# TuringBack.net
KiCad netlist of a schematic drawn in EAGLE
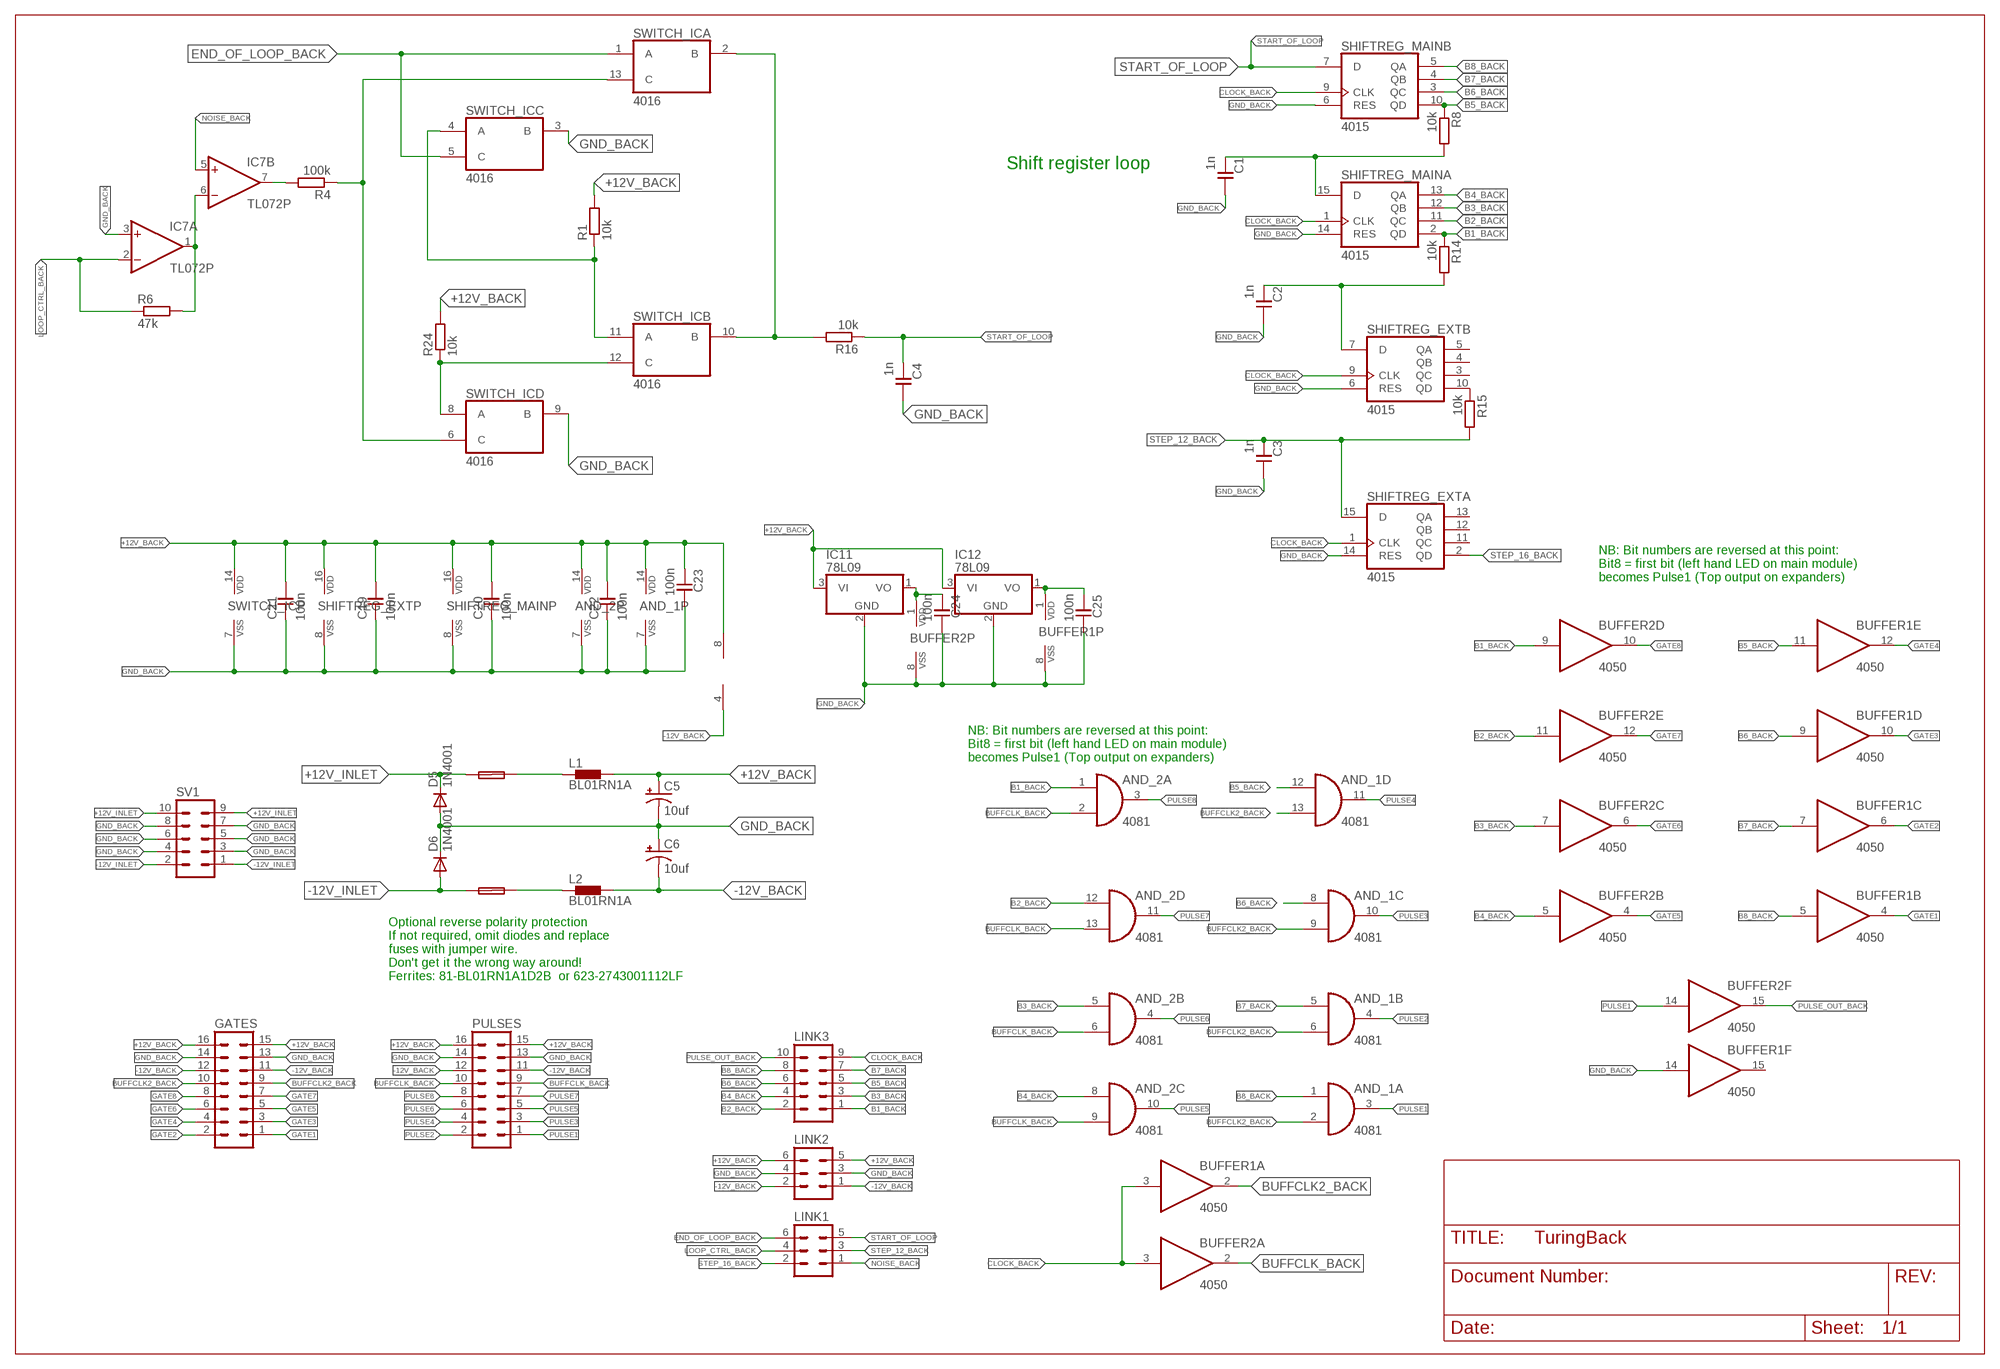
[diagram p0: schematic, sheet 1]

(export (version "E")
  (design (tool "Eeschema 10.0.6"))
  (components
    (comp (ref "+FUSE")
      (value "+FUSE")
      (footprint "eagle-import:C050H075X075")
      (libsource (lib "eagle-import") (part "PTC_FUSEPOLY_FUSE"))
    )
    (comp (ref "-FUSE")
      (value "-FUSE")
      (footprint "eagle-import:C050H075X075")
      (libsource (lib "eagle-import") (part "PTC_FUSEPOLY_FUSE"))
    )
    (comp (ref "AND_1")
      (value "4081")
      (footprint "eagle-import:DIL14")
      (libsource (lib "eagle-import") (part "4081N"))
    )
    (comp (ref "AND_2")
      (value "4081")
      (footprint "eagle-import:DIL14")
      (libsource (lib "eagle-import") (part "4081N"))
    )
    (comp (ref "BUFFER1")
      (value "4050")
      (footprint "eagle-import:DIL16")
      (libsource (lib "eagle-import") (part "4050N"))
    )
    (comp (ref "BUFFER2")
      (value "4050")
      (footprint "eagle-import:DIL16")
      (libsource (lib "eagle-import") (part "4050N"))
    )
    (comp (ref "C1")
      (value "1n")
      (footprint "eagle-import:C050-024X044")
      (libsource (lib "eagle-import") (part "C-EU050-024X044"))
    )
    (comp (ref "C2")
      (value "1n")
      (footprint "eagle-import:C050-024X044")
      (libsource (lib "eagle-import") (part "C-EU050-024X044"))
    )
    (comp (ref "C3")
      (value "1n")
      (footprint "eagle-import:C050-024X044")
      (libsource (lib "eagle-import") (part "C-EU050-024X044"))
    )
    (comp (ref "C4")
      (value "1n")
      (footprint "eagle-import:C050-024X044")
      (libsource (lib "eagle-import") (part "C-EU050-024X044"))
    )
    (comp (ref "C5")
      (value "10uf")
      (footprint "eagle-import:CPOL-RADIAL-10UF-25V")
      (libsource (lib "eagle-import") (part "CAP_POLPTH2"))
    )
    (comp (ref "C6")
      (value "10uf")
      (footprint "eagle-import:CPOL-RADIAL-10UF-25V")
      (libsource (lib "eagle-import") (part "CAP_POLPTH2"))
    )
    (comp (ref "C19")
      (value "100n")
      (footprint "eagle-import:C050-024X044")
      (libsource (lib "eagle-import") (part "C-EU050-024X044"))
    )
    (comp (ref "C20")
      (value "100n")
      (footprint "eagle-import:C050-024X044")
      (libsource (lib "eagle-import") (part "C-EU050-024X044"))
    )
    (comp (ref "C21")
      (value "100n")
      (footprint "eagle-import:C050-024X044")
      (libsource (lib "eagle-import") (part "C-EU050-024X044"))
    )
    (comp (ref "C22")
      (value "100n")
      (footprint "eagle-import:C050-024X044")
      (libsource (lib "eagle-import") (part "C-EU050-024X044"))
    )
    (comp (ref "C23")
      (value "100n")
      (footprint "eagle-import:C050-024X044")
      (libsource (lib "eagle-import") (part "C-EU050-024X044"))
    )
    (comp (ref "C24")
      (value "100n")
      (footprint "eagle-import:C050-024X044")
      (libsource (lib "eagle-import") (part "C-EU050-024X044"))
    )
    (comp (ref "C25")
      (value "100n")
      (footprint "eagle-import:C050-024X044")
      (libsource (lib "eagle-import") (part "C-EU050-024X044"))
    )
    (comp (ref "D5")
      (value "1N4001")
      (footprint "eagle-import:DO41-10")
      (libsource (lib "eagle-import") (part "1N4004"))
    )
    (comp (ref "D6")
      (value "1N4001")
      (footprint "eagle-import:DO41-10")
      (libsource (lib "eagle-import") (part "1N4004"))
    )
    (comp (ref "GATES")
      (value "MA08-2")
      (footprint "eagle-import:MA08-2")
      (libsource (lib "eagle-import") (part "MA08-2"))
    )
    (comp (ref "IC7")
      (value "TL072P")
      (footprint "eagle-import:DIL08")
      (libsource (lib "eagle-import") (part "TL072P"))
    )
    (comp (ref "IC11")
      (value "78L09")
      (footprint "eagle-import:TO92")
      (libsource (lib "eagle-import") (part "78L08"))
    )
    (comp (ref "IC12")
      (value "78L09")
      (footprint "eagle-import:TO92")
      (libsource (lib "eagle-import") (part "78L08"))
    )
    (comp (ref "L1")
      (value "BL01RN1A")
      (footprint "eagle-import:BL01RN1A")
      (libsource (lib "eagle-import") (part "BL01RN1A"))
    )
    (comp (ref "L2")
      (value "BL01RN1A")
      (footprint "eagle-import:BL01RN1A")
      (libsource (lib "eagle-import") (part "BL01RN1A"))
    )
    (comp (ref "LINK1")
      (value "MA03-2")
      (footprint "eagle-import:MA03-2")
      (libsource (lib "eagle-import") (part "MA03-2"))
    )
    (comp (ref "LINK2")
      (value "MA03-2")
      (footprint "eagle-import:MA03-2")
      (libsource (lib "eagle-import") (part "MA03-2"))
    )
    (comp (ref "LINK3")
      (value "MA05-2")
      (footprint "eagle-import:MA05-2")
      (libsource (lib "eagle-import") (part "MA05-2"))
    )
    (comp (ref "PULSES")
      (value "MA08-2")
      (footprint "eagle-import:MA08-2")
      (libsource (lib "eagle-import") (part "MA08-2"))
    )
    (comp (ref "R1")
      (value "10k")
      (footprint "eagle-import:0207_7")
      (libsource (lib "eagle-import") (part "R-EU_0207/7"))
    )
    (comp (ref "R4")
      (value "100k")
      (footprint "eagle-import:0207_7")
      (libsource (lib "eagle-import") (part "R-EU_0207/7"))
    )
    (comp (ref "R6")
      (value "47k")
      (footprint "eagle-import:0207_7")
      (libsource (lib "eagle-import") (part "R-EU_0207/7"))
    )
    (comp (ref "R8")
      (value "10k")
      (footprint "eagle-import:0207_7")
      (libsource (lib "eagle-import") (part "R-EU_0207/7"))
    )
    (comp (ref "R14")
      (value "10k")
      (footprint "eagle-import:0207_7")
      (libsource (lib "eagle-import") (part "R-EU_0207/7"))
    )
    (comp (ref "R15")
      (value "10k")
      (footprint "eagle-import:0207_7")
      (libsource (lib "eagle-import") (part "R-EU_0207/7"))
    )
    (comp (ref "R16")
      (value "10k")
      (footprint "eagle-import:0207_7")
      (libsource (lib "eagle-import") (part "R-EU_0207/7"))
    )
    (comp (ref "R24")
      (value "10k")
      (footprint "eagle-import:0207_7")
      (libsource (lib "eagle-import") (part "R-EU_0207/7"))
    )
    (comp (ref "SHIFTREG_EXT")
      (value "4015")
      (footprint "eagle-import:DIL16")
      (libsource (lib "eagle-import") (part "4015N"))
    )
    (comp (ref "SHIFTREG_MAIN")
      (value "4015")
      (footprint "eagle-import:DIL16")
      (libsource (lib "eagle-import") (part "4015N"))
    )
    (comp (ref "SV1")
      (value "10_PIN_HEADER")
      (footprint "eagle-import:MA05-2")
      (libsource (lib "eagle-import") (part "10_PIN_HEADER"))
    )
    (comp (ref "SWITCH_IC")
      (value "4016")
      (footprint "eagle-import:DIL14")
      (libsource (lib "eagle-import") (part "4016N"))
    )
  )
  (nets
    (net (code "1") (name "+12V_BACK") (class "Default")
      (node (ref "AND_1") (pin "14") (pinfunction "VDD_14") (pintype "power_in"))
      (node (ref "AND_2") (pin "14") (pinfunction "VDD_14") (pintype "power_in"))
      (node (ref "C19") (pin "1") (pinfunction "1_1") (pintype "passive"))
      (node (ref "C20") (pin "1") (pinfunction "1_1") (pintype "passive"))
      (node (ref "C21") (pin "1") (pinfunction "1_1") (pintype "passive"))
      (node (ref "C22") (pin "1") (pinfunction "1_1") (pintype "passive"))
      (node (ref "C23") (pin "2") (pinfunction "2_2") (pintype "passive"))
      (node (ref "C5") (pin "1") (pinfunction "+_1") (pintype "passive"))
      (node (ref "GATES") (pin "15") (pinfunction "15_15") (pintype "passive"))
      (node (ref "GATES") (pin "16") (pinfunction "16_16") (pintype "passive"))
      (node (ref "IC11") (pin "3") (pinfunction "VI_3") (pintype "input"))
      (node (ref "IC12") (pin "3") (pinfunction "VI_3") (pintype "input"))
      (node (ref "IC7") (pin "8") (pinfunction "V+_8") (pintype "power_in"))
      (node (ref "L1") (pin "2") (pinfunction "2_2") (pintype "passive"))
      (node (ref "LINK2") (pin "5") (pinfunction "5_5") (pintype "passive"))
      (node (ref "LINK2") (pin "6") (pinfunction "6_6") (pintype "passive"))
      (node (ref "PULSES") (pin "15") (pinfunction "15_15") (pintype "passive"))
      (node (ref "PULSES") (pin "16") (pinfunction "16_16") (pintype "passive"))
      (node (ref "R1") (pin "2") (pinfunction "2_2") (pintype "passive"))
      (node (ref "R24") (pin "2") (pinfunction "2_2") (pintype "passive"))
      (node (ref "SHIFTREG_EXT") (pin "16") (pinfunction "VDD_16") (pintype "power_in"))
      (node (ref "SHIFTREG_MAIN") (pin "16") (pinfunction "VDD_16") (pintype "power_in"))
      (node (ref "SWITCH_IC") (pin "14") (pinfunction "VDD_14") (pintype "power_in"))
    )
    (net (code "2") (name "+12V_INLET") (class "Default")
      (node (ref "+FUSE") (pin "1") (pinfunction "P$1_1") (pintype "bidirectional"))
      (node (ref "D5") (pin "C") (pinfunction "C_C") (pintype "passive"))
      (node (ref "SV1") (pin "10") (pinfunction "10_10") (pintype "passive"))
      (node (ref "SV1") (pin "9") (pinfunction "9_9") (pintype "passive"))
    )
    (net (code "3") (name "-12V_BACK") (class "Default")
      (node (ref "C6") (pin "2") (pinfunction "-_2") (pintype "passive"))
      (node (ref "GATES") (pin "11") (pinfunction "11_11") (pintype "passive"))
      (node (ref "GATES") (pin "12") (pinfunction "12_12") (pintype "passive"))
      (node (ref "IC7") (pin "4") (pinfunction "V-_4") (pintype "power_in"))
      (node (ref "L2") (pin "2") (pinfunction "2_2") (pintype "passive"))
      (node (ref "LINK2") (pin "1") (pinfunction "1_1") (pintype "passive"))
      (node (ref "LINK2") (pin "2") (pinfunction "2_2") (pintype "passive"))
      (node (ref "PULSES") (pin "11") (pinfunction "11_11") (pintype "passive"))
      (node (ref "PULSES") (pin "12") (pinfunction "12_12") (pintype "passive"))
    )
    (net (code "4") (name "-12V_INLET") (class "Default")
      (node (ref "-FUSE") (pin "1") (pinfunction "P$1_1") (pintype "bidirectional"))
      (node (ref "D6") (pin "A") (pinfunction "A_A") (pintype "passive"))
      (node (ref "SV1") (pin "1") (pinfunction "1_1") (pintype "passive"))
      (node (ref "SV1") (pin "2") (pinfunction "2_2") (pintype "passive"))
    )
    (net (code "5") (name "B1_BACK") (class "Default")
      (node (ref "AND_2") (pin "1") (pinfunction "I0_1") (pintype "input"))
      (node (ref "BUFFER2") (pin "9") (pinfunction "I_9") (pintype "input"))
      (node (ref "LINK3") (pin "1") (pinfunction "1_1") (pintype "passive"))
      (node (ref "R14") (pin "1") (pinfunction "1_1") (pintype "passive"))
      (node (ref "SHIFTREG_MAIN") (pin "2") (pinfunction "QD_2") (pintype "output"))
    )
    (net (code "6") (name "B2_BACK") (class "Default")
      (node (ref "AND_2") (pin "12") (pinfunction "I0_12") (pintype "input"))
      (node (ref "BUFFER2") (pin "11") (pinfunction "I_11") (pintype "input"))
      (node (ref "LINK3") (pin "2") (pinfunction "2_2") (pintype "passive"))
      (node (ref "SHIFTREG_MAIN") (pin "11") (pinfunction "QC_11") (pintype "output"))
    )
    (net (code "7") (name "B3_BACK") (class "Default")
      (node (ref "AND_2") (pin "5") (pinfunction "I0_5") (pintype "input"))
      (node (ref "BUFFER2") (pin "7") (pinfunction "I_7") (pintype "input"))
      (node (ref "LINK3") (pin "3") (pinfunction "3_3") (pintype "passive"))
      (node (ref "SHIFTREG_MAIN") (pin "12") (pinfunction "QB_12") (pintype "output"))
    )
    (net (code "8") (name "B4_BACK") (class "Default")
      (node (ref "AND_2") (pin "8") (pinfunction "I0_8") (pintype "input"))
      (node (ref "BUFFER2") (pin "5") (pinfunction "I_5") (pintype "input"))
      (node (ref "LINK3") (pin "4") (pinfunction "4_4") (pintype "passive"))
      (node (ref "SHIFTREG_MAIN") (pin "13") (pinfunction "QA_13") (pintype "output"))
    )
    (net (code "9") (name "B5_BACK") (class "Default")
      (node (ref "AND_1") (pin "12") (pinfunction "I0_12") (pintype "input"))
      (node (ref "BUFFER1") (pin "11") (pinfunction "I_11") (pintype "input"))
      (node (ref "LINK3") (pin "5") (pinfunction "5_5") (pintype "passive"))
      (node (ref "R8") (pin "1") (pinfunction "1_1") (pintype "passive"))
      (node (ref "SHIFTREG_MAIN") (pin "10") (pinfunction "QD_10") (pintype "output"))
    )
    (net (code "10") (name "B6_BACK") (class "Default")
      (node (ref "AND_1") (pin "8") (pinfunction "I0_8") (pintype "input"))
      (node (ref "BUFFER1") (pin "9") (pinfunction "I_9") (pintype "input"))
      (node (ref "LINK3") (pin "6") (pinfunction "6_6") (pintype "passive"))
      (node (ref "SHIFTREG_MAIN") (pin "3") (pinfunction "QC_3") (pintype "output"))
    )
    (net (code "11") (name "B7_BACK") (class "Default")
      (node (ref "AND_1") (pin "5") (pinfunction "I0_5") (pintype "input"))
      (node (ref "BUFFER1") (pin "7") (pinfunction "I_7") (pintype "input"))
      (node (ref "LINK3") (pin "7") (pinfunction "7_7") (pintype "passive"))
      (node (ref "SHIFTREG_MAIN") (pin "4") (pinfunction "QB_4") (pintype "output"))
    )
    (net (code "12") (name "B8_BACK") (class "Default")
      (node (ref "AND_1") (pin "1") (pinfunction "I0_1") (pintype "input"))
      (node (ref "BUFFER1") (pin "5") (pinfunction "I_5") (pintype "input"))
      (node (ref "LINK3") (pin "8") (pinfunction "8_8") (pintype "passive"))
      (node (ref "SHIFTREG_MAIN") (pin "5") (pinfunction "QA_5") (pintype "output"))
    )
    (net (code "13") (name "BUFFCLK2_BACK") (class "Default")
      (node (ref "AND_1") (pin "13") (pinfunction "I1_13") (pintype "input"))
      (node (ref "AND_1") (pin "2") (pinfunction "I1_2") (pintype "input"))
      (node (ref "AND_1") (pin "6") (pinfunction "I1_6") (pintype "input"))
      (node (ref "AND_1") (pin "9") (pinfunction "I1_9") (pintype "input"))
      (node (ref "BUFFER1") (pin "2") (pinfunction "O_2") (pintype "output"))
      (node (ref "GATES") (pin "10") (pinfunction "10_10") (pintype "passive"))
      (node (ref "GATES") (pin "9") (pinfunction "9_9") (pintype "passive"))
    )
    (net (code "14") (name "BUFFCLK_BACK") (class "Default")
      (node (ref "AND_2") (pin "13") (pinfunction "I1_13") (pintype "input"))
      (node (ref "AND_2") (pin "2") (pinfunction "I1_2") (pintype "input"))
      (node (ref "AND_2") (pin "6") (pinfunction "I1_6") (pintype "input"))
      (node (ref "AND_2") (pin "9") (pinfunction "I1_9") (pintype "input"))
      (node (ref "BUFFER2") (pin "2") (pinfunction "O_2") (pintype "output"))
      (node (ref "PULSES") (pin "10") (pinfunction "10_10") (pintype "passive"))
      (node (ref "PULSES") (pin "9") (pinfunction "9_9") (pintype "passive"))
    )
    (net (code "15") (name "CLOCK_BACK") (class "Default")
      (node (ref "BUFFER1") (pin "3") (pinfunction "I_3") (pintype "input"))
      (node (ref "BUFFER2") (pin "3") (pinfunction "I_3") (pintype "input"))
      (node (ref "LINK3") (pin "9") (pinfunction "9_9") (pintype "passive"))
      (node (ref "SHIFTREG_EXT") (pin "1") (pinfunction "CLK_1") (pintype "input"))
      (node (ref "SHIFTREG_EXT") (pin "9") (pinfunction "CLK_9") (pintype "input"))
      (node (ref "SHIFTREG_MAIN") (pin "1") (pinfunction "CLK_1") (pintype "input"))
      (node (ref "SHIFTREG_MAIN") (pin "9") (pinfunction "CLK_9") (pintype "input"))
    )
    (net (code "16") (name "END_OF_LOOP_BACK") (class "Default")
      (node (ref "LINK1") (pin "6") (pinfunction "6_6") (pintype "passive"))
      (node (ref "SWITCH_IC") (pin "1") (pinfunction "A_1") (pintype "tri_state"))
      (node (ref "SWITCH_IC") (pin "5") (pinfunction "C_5") (pintype "input"))
    )
    (net (code "17") (name "GATE1") (class "Default")
      (node (ref "BUFFER1") (pin "4") (pinfunction "O_4") (pintype "output"))
      (node (ref "GATES") (pin "1") (pinfunction "1_1") (pintype "passive"))
    )
    (net (code "18") (name "GATE2") (class "Default")
      (node (ref "BUFFER1") (pin "6") (pinfunction "O_6") (pintype "output"))
      (node (ref "GATES") (pin "2") (pinfunction "2_2") (pintype "passive"))
    )
    (net (code "19") (name "GATE3") (class "Default")
      (node (ref "BUFFER1") (pin "10") (pinfunction "O_10") (pintype "output"))
      (node (ref "GATES") (pin "3") (pinfunction "3_3") (pintype "passive"))
    )
    (net (code "20") (name "GATE4") (class "Default")
      (node (ref "BUFFER1") (pin "12") (pinfunction "O_12") (pintype "output"))
      (node (ref "GATES") (pin "4") (pinfunction "4_4") (pintype "passive"))
    )
    (net (code "21") (name "GATE5") (class "Default")
      (node (ref "BUFFER2") (pin "4") (pinfunction "O_4") (pintype "output"))
      (node (ref "GATES") (pin "5") (pinfunction "5_5") (pintype "passive"))
    )
    (net (code "22") (name "GATE6") (class "Default")
      (node (ref "BUFFER2") (pin "6") (pinfunction "O_6") (pintype "output"))
      (node (ref "GATES") (pin "6") (pinfunction "6_6") (pintype "passive"))
    )
    (net (code "23") (name "GATE7") (class "Default")
      (node (ref "BUFFER2") (pin "12") (pinfunction "O_12") (pintype "output"))
      (node (ref "GATES") (pin "7") (pinfunction "7_7") (pintype "passive"))
    )
    (net (code "24") (name "GATE8") (class "Default")
      (node (ref "BUFFER2") (pin "10") (pinfunction "O_10") (pintype "output"))
      (node (ref "GATES") (pin "8") (pinfunction "8_8") (pintype "passive"))
    )
    (net (code "25") (name "GND_BACK") (class "Default")
      (node (ref "AND_1") (pin "7") (pinfunction "VSS_7") (pintype "power_in"))
      (node (ref "AND_2") (pin "7") (pinfunction "VSS_7") (pintype "power_in"))
      (node (ref "BUFFER1") (pin "14") (pinfunction "I_14") (pintype "input"))
      (node (ref "BUFFER1") (pin "8") (pinfunction "VSS_8") (pintype "power_in"))
      (node (ref "BUFFER2") (pin "8") (pinfunction "VSS_8") (pintype "power_in"))
      (node (ref "C1") (pin "1") (pinfunction "1_1") (pintype "passive"))
      (node (ref "C19") (pin "2") (pinfunction "2_2") (pintype "passive"))
      (node (ref "C2") (pin "1") (pinfunction "1_1") (pintype "passive"))
      (node (ref "C20") (pin "2") (pinfunction "2_2") (pintype "passive"))
      (node (ref "C21") (pin "2") (pinfunction "2_2") (pintype "passive"))
      (node (ref "C22") (pin "2") (pinfunction "2_2") (pintype "passive"))
      (node (ref "C23") (pin "1") (pinfunction "1_1") (pintype "passive"))
      (node (ref "C24") (pin "1") (pinfunction "1_1") (pintype "passive"))
      (node (ref "C25") (pin "1") (pinfunction "1_1") (pintype "passive"))
      (node (ref "C3") (pin "1") (pinfunction "1_1") (pintype "passive"))
      (node (ref "C4") (pin "1") (pinfunction "1_1") (pintype "passive"))
      (node (ref "C5") (pin "2") (pinfunction "-_2") (pintype "passive"))
      (node (ref "C6") (pin "1") (pinfunction "+_1") (pintype "passive"))
      (node (ref "D5") (pin "A") (pinfunction "A_A") (pintype "passive"))
      (node (ref "D6") (pin "C") (pinfunction "C_C") (pintype "passive"))
      (node (ref "GATES") (pin "13") (pinfunction "13_13") (pintype "passive"))
      (node (ref "GATES") (pin "14") (pinfunction "14_14") (pintype "passive"))
      (node (ref "IC11") (pin "2") (pinfunction "GND_2") (pintype "passive"))
      (node (ref "IC12") (pin "2") (pinfunction "GND_2") (pintype "passive"))
      (node (ref "IC7") (pin "3") (pinfunction "+IN_3") (pintype "input"))
      (node (ref "LINK2") (pin "3") (pinfunction "3_3") (pintype "passive"))
      (node (ref "LINK2") (pin "4") (pinfunction "4_4") (pintype "passive"))
      (node (ref "PULSES") (pin "13") (pinfunction "13_13") (pintype "passive"))
      (node (ref "PULSES") (pin "14") (pinfunction "14_14") (pintype "passive"))
      (node (ref "SHIFTREG_EXT") (pin "14") (pinfunction "RES_14") (pintype "input"))
      (node (ref "SHIFTREG_EXT") (pin "6") (pinfunction "RES_6") (pintype "input"))
      (node (ref "SHIFTREG_EXT") (pin "8") (pinfunction "VSS_8") (pintype "power_in"))
      (node (ref "SHIFTREG_MAIN") (pin "14") (pinfunction "RES_14") (pintype "input"))
      (node (ref "SHIFTREG_MAIN") (pin "6") (pinfunction "RES_6") (pintype "input"))
      (node (ref "SHIFTREG_MAIN") (pin "8") (pinfunction "VSS_8") (pintype "power_in"))
      (node (ref "SV1") (pin "3") (pinfunction "3_3") (pintype "passive"))
      (node (ref "SV1") (pin "4") (pinfunction "4_4") (pintype "passive"))
      (node (ref "SV1") (pin "5") (pinfunction "5_5") (pintype "passive"))
      (node (ref "SV1") (pin "6") (pinfunction "6_6") (pintype "passive"))
      (node (ref "SV1") (pin "7") (pinfunction "7_7") (pintype "passive"))
      (node (ref "SV1") (pin "8") (pinfunction "8_8") (pintype "passive"))
      (node (ref "SWITCH_IC") (pin "3") (pinfunction "B_3") (pintype "tri_state"))
      (node (ref "SWITCH_IC") (pin "7") (pinfunction "VSS_7") (pintype "power_in"))
      (node (ref "SWITCH_IC") (pin "9") (pinfunction "B_9") (pintype "tri_state"))
    )
    (net (code "26") (name "LOOP_CTRL_BACK") (class "Default")
      (node (ref "IC7") (pin "2") (pinfunction "-IN_2") (pintype "input"))
      (node (ref "LINK1") (pin "4") (pinfunction "4_4") (pintype "passive"))
      (node (ref "R6") (pin "1") (pinfunction "1_1") (pintype "passive"))
    )
    (net (code "27") (name "NOISE_BACK") (class "Default")
      (node (ref "IC7") (pin "5") (pinfunction "+IN_5") (pintype "input"))
      (node (ref "LINK1") (pin "1") (pinfunction "1_1") (pintype "passive"))
    )
    (net (code "28") (name "Net-(+FUSE-P$2)") (class "Default")
      (node (ref "+FUSE") (pin "2") (pinfunction "P$2_2") (pintype "bidirectional"))
      (node (ref "L1") (pin "1") (pinfunction "1_1") (pintype "passive"))
    )
    (net (code "29") (name "Net-(-FUSE-P$2)") (class "Default")
      (node (ref "-FUSE") (pin "2") (pinfunction "P$2_2") (pintype "bidirectional"))
      (node (ref "L2") (pin "1") (pinfunction "1_1") (pintype "passive"))
    )
    (net (code "30") (name "Net-(BUFFER1G-VDD)") (class "Default")
      (node (ref "BUFFER1") (pin "1") (pinfunction "VDD_1") (pintype "power_in"))
      (node (ref "C25") (pin "2") (pinfunction "2_2") (pintype "passive"))
      (node (ref "IC12") (pin "1") (pinfunction "VO_1") (pintype "passive"))
    )
    (net (code "31") (name "Net-(BUFFER2G-VDD)") (class "Default")
      (node (ref "BUFFER2") (pin "1") (pinfunction "VDD_1") (pintype "power_in"))
      (node (ref "C24") (pin "2") (pinfunction "2_2") (pintype "passive"))
      (node (ref "IC11") (pin "1") (pinfunction "VO_1") (pintype "passive"))
    )
    (net (code "32") (name "Net-(IC7A-OUT)") (class "Default")
      (node (ref "IC7") (pin "1") (pinfunction "OUT_1") (pintype "output"))
      (node (ref "IC7") (pin "6") (pinfunction "-IN_6") (pintype "input"))
      (node (ref "R6") (pin "2") (pinfunction "2_2") (pintype "passive"))
    )
    (net (code "33") (name "Net-(IC7B-OUT)") (class "Default")
      (node (ref "IC7") (pin "7") (pinfunction "OUT_7") (pintype "output"))
      (node (ref "R4") (pin "2") (pinfunction "2_2") (pintype "passive"))
    )
    (net (code "34") (name "Net-(SHIFTREG_EXTB-D)") (class "Default")
      (node (ref "C2") (pin "2") (pinfunction "2_2") (pintype "passive"))
      (node (ref "R14") (pin "2") (pinfunction "2_2") (pintype "passive"))
      (node (ref "SHIFTREG_EXT") (pin "7") (pinfunction "D_7") (pintype "input"))
    )
    (net (code "35") (name "Net-(SHIFTREG_EXTB-QD)") (class "Default")
      (node (ref "R15") (pin "1") (pinfunction "1_1") (pintype "passive"))
      (node (ref "SHIFTREG_EXT") (pin "10") (pinfunction "QD_10") (pintype "output"))
    )
    (net (code "36") (name "Net-(SHIFTREG_MAINA-D)") (class "Default")
      (node (ref "C1") (pin "2") (pinfunction "2_2") (pintype "passive"))
      (node (ref "R8") (pin "2") (pinfunction "2_2") (pintype "passive"))
      (node (ref "SHIFTREG_MAIN") (pin "15") (pinfunction "D_15") (pintype "input"))
    )
    (net (code "37") (name "Net-(SWITCH_ICA-B)") (class "Default")
      (node (ref "R16") (pin "2") (pinfunction "2_2") (pintype "passive"))
      (node (ref "SWITCH_IC") (pin "10") (pinfunction "B_10") (pintype "tri_state"))
      (node (ref "SWITCH_IC") (pin "2") (pinfunction "B_2") (pintype "tri_state"))
    )
    (net (code "38") (name "Net-(SWITCH_ICA-C)") (class "Default")
      (node (ref "R4") (pin "1") (pinfunction "1_1") (pintype "passive"))
      (node (ref "SWITCH_IC") (pin "13") (pinfunction "C_13") (pintype "input"))
      (node (ref "SWITCH_IC") (pin "6") (pinfunction "C_6") (pintype "input"))
    )
    (net (code "39") (name "Net-(SWITCH_ICB-A)") (class "Default")
      (node (ref "R1") (pin "1") (pinfunction "1_1") (pintype "passive"))
      (node (ref "SWITCH_IC") (pin "11") (pinfunction "A_11") (pintype "tri_state"))
      (node (ref "SWITCH_IC") (pin "4") (pinfunction "A_4") (pintype "tri_state"))
    )
    (net (code "40") (name "Net-(SWITCH_ICB-C)") (class "Default")
      (node (ref "R24") (pin "1") (pinfunction "1_1") (pintype "passive"))
      (node (ref "SWITCH_IC") (pin "12") (pinfunction "C_12") (pintype "input"))
      (node (ref "SWITCH_IC") (pin "8") (pinfunction "A_8") (pintype "tri_state"))
    )
    (net (code "41") (name "PULSE1") (class "Default")
      (node (ref "AND_1") (pin "3") (pinfunction "O_3") (pintype "output"))
      (node (ref "BUFFER2") (pin "14") (pinfunction "I_14") (pintype "input"))
      (node (ref "PULSES") (pin "1") (pinfunction "1_1") (pintype "passive"))
    )
    (net (code "42") (name "PULSE2") (class "Default")
      (node (ref "AND_1") (pin "4") (pinfunction "O_4") (pintype "output"))
      (node (ref "PULSES") (pin "2") (pinfunction "2_2") (pintype "passive"))
    )
    (net (code "43") (name "PULSE3") (class "Default")
      (node (ref "AND_1") (pin "10") (pinfunction "O_10") (pintype "output"))
      (node (ref "PULSES") (pin "3") (pinfunction "3_3") (pintype "passive"))
    )
    (net (code "44") (name "PULSE4") (class "Default")
      (node (ref "AND_1") (pin "11") (pinfunction "O_11") (pintype "output"))
      (node (ref "PULSES") (pin "4") (pinfunction "4_4") (pintype "passive"))
    )
    (net (code "45") (name "PULSE5") (class "Default")
      (node (ref "AND_2") (pin "10") (pinfunction "O_10") (pintype "output"))
      (node (ref "PULSES") (pin "5") (pinfunction "5_5") (pintype "passive"))
    )
    (net (code "46") (name "PULSE6") (class "Default")
      (node (ref "AND_2") (pin "4") (pinfunction "O_4") (pintype "output"))
      (node (ref "PULSES") (pin "6") (pinfunction "6_6") (pintype "passive"))
    )
    (net (code "47") (name "PULSE7") (class "Default")
      (node (ref "AND_2") (pin "11") (pinfunction "O_11") (pintype "output"))
      (node (ref "PULSES") (pin "7") (pinfunction "7_7") (pintype "passive"))
    )
    (net (code "48") (name "PULSE8") (class "Default")
      (node (ref "AND_2") (pin "3") (pinfunction "O_3") (pintype "output"))
      (node (ref "PULSES") (pin "8") (pinfunction "8_8") (pintype "passive"))
    )
    (net (code "49") (name "PULSE_OUT_BACK") (class "Default")
      (node (ref "BUFFER2") (pin "15") (pinfunction "O_15") (pintype "output"))
      (node (ref "LINK3") (pin "10") (pinfunction "10_10") (pintype "passive"))
    )
    (net (code "50") (name "START_OF_LOOP") (class "Default")
      (node (ref "C4") (pin "2") (pinfunction "2_2") (pintype "passive"))
      (node (ref "LINK1") (pin "5") (pinfunction "5_5") (pintype "passive"))
      (node (ref "R16") (pin "1") (pinfunction "1_1") (pintype "passive"))
      (node (ref "SHIFTREG_MAIN") (pin "7") (pinfunction "D_7") (pintype "input"))
    )
    (net (code "51") (name "STEP_12_BACK") (class "Default")
      (node (ref "C3") (pin "2") (pinfunction "2_2") (pintype "passive"))
      (node (ref "LINK1") (pin "3") (pinfunction "3_3") (pintype "passive"))
      (node (ref "R15") (pin "2") (pinfunction "2_2") (pintype "passive"))
      (node (ref "SHIFTREG_EXT") (pin "15") (pinfunction "D_15") (pintype "input"))
    )
    (net (code "52") (name "STEP_16_BACK") (class "Default")
      (node (ref "LINK1") (pin "2") (pinfunction "2_2") (pintype "passive"))
      (node (ref "SHIFTREG_EXT") (pin "2") (pinfunction "QD_2") (pintype "output"))
    )
    (net (code "53") (name "unconnected-(BUFFER1F-O-Pad15)") (class "Default")
      (node (ref "BUFFER1") (pin "15") (pinfunction "O_15") (pintype "output"))
    )
    (net (code "54") (name "unconnected-(SHIFTREG_EXTA-QA-Pad13)") (class "Default")
      (node (ref "SHIFTREG_EXT") (pin "13") (pinfunction "QA_13") (pintype "output"))
    )
    (net (code "55") (name "unconnected-(SHIFTREG_EXTA-QB-Pad12)") (class "Default")
      (node (ref "SHIFTREG_EXT") (pin "12") (pinfunction "QB_12") (pintype "output"))
    )
    (net (code "56") (name "unconnected-(SHIFTREG_EXTA-QC-Pad11)") (class "Default")
      (node (ref "SHIFTREG_EXT") (pin "11") (pinfunction "QC_11") (pintype "output"))
    )
    (net (code "57") (name "unconnected-(SHIFTREG_EXTB-QA-Pad5)") (class "Default")
      (node (ref "SHIFTREG_EXT") (pin "5") (pinfunction "QA_5") (pintype "output"))
    )
    (net (code "58") (name "unconnected-(SHIFTREG_EXTB-QB-Pad4)") (class "Default")
      (node (ref "SHIFTREG_EXT") (pin "4") (pinfunction "QB_4") (pintype "output"))
    )
    (net (code "59") (name "unconnected-(SHIFTREG_EXTB-QC-Pad3)") (class "Default")
      (node (ref "SHIFTREG_EXT") (pin "3") (pinfunction "QC_3") (pintype "output"))
    )
  )
)
